# heights-no-branding.net
KiCad netlist of a schematic drawn in EAGLE
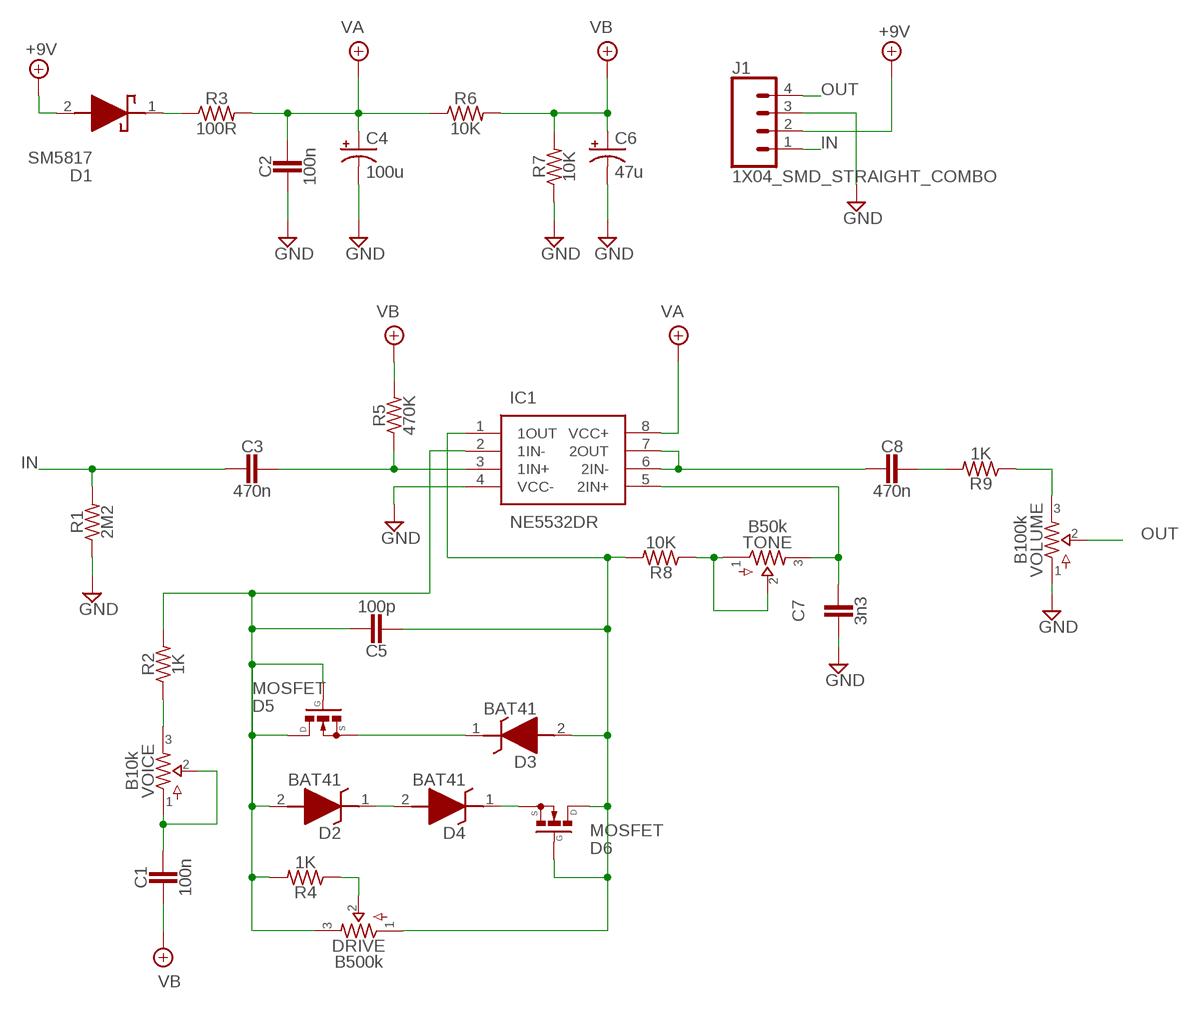
[diagram p0: schematic, sheet 1]

(export (version "E")
  (design (tool "Eeschema 10.0.6"))
  (components
    (comp (ref "C1")
      (value "100n")
      (footprint "eagle-import:RESISTOR_C1206")
      (libsource (lib "eagle-import") (part "CAP1206"))
    )
    (comp (ref "C2")
      (value "100n")
      (footprint "eagle-import:RESISTOR_R0603")
      (libsource (lib "eagle-import") (part "CAP0603"))
    )
    (comp (ref "C3")
      (value "470n")
      (footprint "eagle-import:RESISTOR_C1206")
      (libsource (lib "eagle-import") (part "CAP1206"))
    )
    (comp (ref "C4")
      (value "100u")
      (footprint "eagle-import:063_025")
      (libsource (lib "eagle-import") (part "0631"))
    )
    (comp (ref "C5")
      (value "100p")
      (footprint "eagle-import:RESISTOR_R0603")
      (libsource (lib "eagle-import") (part "CAP0603"))
    )
    (comp (ref "C6")
      (value "47u")
      (footprint "eagle-import:050_020_1")
      (libsource (lib "eagle-import") (part "0501"))
    )
    (comp (ref "C7")
      (value "3n3")
      (footprint "eagle-import:RESISTOR_R0603")
      (libsource (lib "eagle-import") (part "CAP0603"))
    )
    (comp (ref "C8")
      (value "470n")
      (footprint "eagle-import:RESISTOR_C1206")
      (libsource (lib "eagle-import") (part "CAP1206"))
    )
    (comp (ref "D1")
      (value "SM5817")
      (footprint "eagle-import:SOD3716X120N")
      (fields
        (field (name "MANUFACTURER_PART_NUMBER") "SM5817PL-TP")
        (field (name "MOUSER_PART_NUMBER") "833-SM5817PL-TP")
      )
      (libsource (lib "eagle-import") (part "SM5817PL-TP"))
    )
    (comp (ref "D2")
      (value "BAT41")
      (footprint "eagle-import:SODFL3718X130N")
      (fields
        (field (name "MANUFACTURER_PART_NUMBER") "MM1Z4733A")
        (field (name "MOUSER_PART_NUMBER") "637-MM1Z4733A")
      )
      (libsource (lib "eagle-import") (part "MM1Z4733A"))
    )
    (comp (ref "D3")
      (value "BAT41")
      (footprint "eagle-import:SODFL3718X130N")
      (fields
        (field (name "MANUFACTURER_PART_NUMBER") "MM1Z4733A")
        (field (name "MOUSER_PART_NUMBER") "637-MM1Z4733A")
      )
      (libsource (lib "eagle-import") (part "MM1Z4733A"))
    )
    (comp (ref "D4")
      (value "BAT41")
      (footprint "eagle-import:SODFL3718X130N")
      (fields
        (field (name "MANUFACTURER_PART_NUMBER") "MM1Z4733A")
        (field (name "MOUSER_PART_NUMBER") "637-MM1Z4733A")
      )
      (libsource (lib "eagle-import") (part "MM1Z4733A"))
    )
    (comp (ref "D5")
      (value "MOSFET")
      (footprint "eagle-import:TRANSISTOR_SOT23-GDS")
      (libsource (lib "eagle-import") (part "MOSFET"))
    )
    (comp (ref "D6")
      (value "MOSFET")
      (footprint "eagle-import:TRANSISTOR_SOT23-GDS")
      (libsource (lib "eagle-import") (part "MOSFET"))
    )
    (comp (ref "DRIVE")
      (value "B500k")
      (footprint "eagle-import:16MM_B.MOUNT")
      (libsource (lib "eagle-import") (part "16MM.1"))
    )
    (comp (ref "IC1")
      (value "NE5532DR")
      (footprint "eagle-import:SOIC127P600X175-8N")
      (fields (field (name "MOUSER_PART_NUMBER") "595-NE5532DR"))
      (libsource (lib "eagle-import") (part "NE5532DR"))
    )
    (comp (ref "J1")
      (value "1X04_SMD_STRAIGHT_COMBO")
      (footprint "eagle-import:1X04")
      (libsource (lib "eagle-import") (part "CONN_04PTH"))
    )
    (comp (ref "R1")
      (value "2M2")
      (footprint "eagle-import:RESISTOR_R0603")
      (libsource (lib "eagle-import") (part "RESISTOR0603"))
    )
    (comp (ref "R2")
      (value "1K")
      (footprint "eagle-import:RESISTOR_R0603")
      (libsource (lib "eagle-import") (part "RESISTOR0603"))
    )
    (comp (ref "R3")
      (value "100R")
      (footprint "eagle-import:RESISTOR_R0603")
      (libsource (lib "eagle-import") (part "RESISTOR0603"))
    )
    (comp (ref "R4")
      (value "1K")
      (footprint "eagle-import:RESISTOR_R0603")
      (libsource (lib "eagle-import") (part "RESISTOR0603"))
    )
    (comp (ref "R5")
      (value "470K")
      (footprint "eagle-import:RESISTOR_R0603")
      (libsource (lib "eagle-import") (part "RESISTOR0603"))
    )
    (comp (ref "R6")
      (value "10K")
      (footprint "eagle-import:RESISTOR_R0603")
      (libsource (lib "eagle-import") (part "RESISTOR0603"))
    )
    (comp (ref "R7")
      (value "10K")
      (footprint "eagle-import:RESISTOR_R0603")
      (libsource (lib "eagle-import") (part "RESISTOR0603"))
    )
    (comp (ref "R8")
      (value "10K")
      (footprint "eagle-import:RESISTOR_R0603")
      (libsource (lib "eagle-import") (part "RESISTOR0603"))
    )
    (comp (ref "R9")
      (value "1K")
      (footprint "eagle-import:RESISTOR_R0603")
      (libsource (lib "eagle-import") (part "RESISTOR0603"))
    )
    (comp (ref "TONE")
      (value "B50k")
      (footprint "eagle-import:16MM_B.MOUNT")
      (libsource (lib "eagle-import") (part "16MM.1"))
    )
    (comp (ref "VOICE")
      (value "B10k")
      (footprint "eagle-import:16MM_B.MOUNT")
      (libsource (lib "eagle-import") (part "16MM.1"))
    )
    (comp (ref "VOLUME")
      (value "B100k")
      (footprint "eagle-import:16MM_B.MOUNT")
      (libsource (lib "eagle-import") (part "16MM.1"))
    )
  )
  (nets
    (net (code "1") (name "+9V") (class "Default")
      (node (ref "D1") (pin "2") (pinfunction "A_2") (pintype "bidirectional"))
      (node (ref "J1") (pin "2") (pinfunction "2_2") (pintype "passive"))
    )
    (net (code "2") (name "/IN") (class "Default")
      (node (ref "C3") (pin "2") (pinfunction "2_2") (pintype "passive"))
      (node (ref "J1") (pin "1") (pinfunction "1_1") (pintype "passive"))
      (node (ref "R1") (pin "2") (pinfunction "2_2") (pintype "passive"))
    )
    (net (code "3") (name "/OUT") (class "Default")
      (node (ref "J1") (pin "4") (pinfunction "4_4") (pintype "passive"))
      (node (ref "VOLUME") (pin "2") (pinfunction "2_2") (pintype "passive"))
    )
    (net (code "4") (name "GND") (class "Default")
      (node (ref "C2") (pin "2") (pinfunction "2_2") (pintype "passive"))
      (node (ref "C4") (pin "-") (pinfunction "-_-") (pintype "passive"))
      (node (ref "C6") (pin "-") (pinfunction "-_-") (pintype "passive"))
      (node (ref "C7") (pin "2") (pinfunction "2_2") (pintype "passive"))
      (node (ref "IC1") (pin "4") (pinfunction "VCC-_4") (pintype "bidirectional"))
      (node (ref "J1") (pin "3") (pinfunction "3_3") (pintype "passive"))
      (node (ref "R1") (pin "1") (pinfunction "1_1") (pintype "passive"))
      (node (ref "R7") (pin "1") (pinfunction "1_1") (pintype "passive"))
      (node (ref "VOLUME") (pin "1") (pinfunction "1_1") (pintype "passive"))
    )
    (net (code "5") (name "Net-(C1-Pad1)") (class "Default")
      (node (ref "C1") (pin "1") (pinfunction "1_1") (pintype "passive"))
      (node (ref "VOICE") (pin "1") (pinfunction "1_1") (pintype "passive"))
      (node (ref "VOICE") (pin "2") (pinfunction "2_2") (pintype "passive"))
    )
    (net (code "6") (name "Net-(C8-Pad1)") (class "Default")
      (node (ref "C8") (pin "1") (pinfunction "1_1") (pintype "passive"))
      (node (ref "R9") (pin "2") (pinfunction "2_2") (pintype "passive"))
    )
    (net (code "7") (name "Net-(D1-K)") (class "Default")
      (node (ref "D1") (pin "1") (pinfunction "K_1") (pintype "bidirectional"))
      (node (ref "R3") (pin "1") (pinfunction "1_1") (pintype "passive"))
    )
    (net (code "8") (name "Net-(D2-A)") (class "Default")
      (node (ref "C5") (pin "1") (pinfunction "1_1") (pintype "passive"))
      (node (ref "D2") (pin "2") (pinfunction "A_2") (pintype "bidirectional"))
      (node (ref "D5") (pin "D") (pinfunction "D_D") (pintype "passive"))
      (node (ref "D5") (pin "G") (pinfunction "G_G") (pintype "passive"))
      (node (ref "DRIVE") (pin "3") (pinfunction "3_3") (pintype "passive"))
      (node (ref "IC1") (pin "2") (pinfunction "1IN-_2") (pintype "bidirectional"))
      (node (ref "R2") (pin "2") (pinfunction "2_2") (pintype "passive"))
      (node (ref "R4") (pin "2") (pinfunction "2_2") (pintype "passive"))
    )
    (net (code "9") (name "Net-(D2-K)") (class "Default")
      (node (ref "D2") (pin "1") (pinfunction "K_1") (pintype "bidirectional"))
      (node (ref "D4") (pin "2") (pinfunction "A_2") (pintype "bidirectional"))
    )
    (net (code "10") (name "Net-(D3-A)") (class "Default")
      (node (ref "C5") (pin "2") (pinfunction "2_2") (pintype "passive"))
      (node (ref "D3") (pin "2") (pinfunction "A_2") (pintype "bidirectional"))
      (node (ref "D6") (pin "D") (pinfunction "D_D") (pintype "passive"))
      (node (ref "D6") (pin "G") (pinfunction "G_G") (pintype "passive"))
      (node (ref "DRIVE") (pin "1") (pinfunction "1_1") (pintype "passive"))
      (node (ref "IC1") (pin "1") (pinfunction "1OUT_1") (pintype "bidirectional"))
      (node (ref "R8") (pin "2") (pinfunction "2_2") (pintype "passive"))
    )
    (net (code "11") (name "Net-(D3-K)") (class "Default")
      (node (ref "D3") (pin "1") (pinfunction "K_1") (pintype "bidirectional"))
      (node (ref "D5") (pin "S") (pinfunction "S_S") (pintype "passive"))
    )
    (net (code "12") (name "Net-(D4-K)") (class "Default")
      (node (ref "D4") (pin "1") (pinfunction "K_1") (pintype "bidirectional"))
      (node (ref "D6") (pin "S") (pinfunction "S_S") (pintype "passive"))
    )
    (net (code "13") (name "Net-(DRIVE-Pad2)") (class "Default")
      (node (ref "DRIVE") (pin "2") (pinfunction "2_2") (pintype "passive"))
      (node (ref "R4") (pin "1") (pinfunction "1_1") (pintype "passive"))
    )
    (net (code "14") (name "Net-(IC1-1IN+)") (class "Default")
      (node (ref "C3") (pin "1") (pinfunction "1_1") (pintype "passive"))
      (node (ref "IC1") (pin "3") (pinfunction "1IN+_3") (pintype "bidirectional"))
      (node (ref "R5") (pin "1") (pinfunction "1_1") (pintype "passive"))
    )
    (net (code "15") (name "Net-(IC1-2IN+)") (class "Default")
      (node (ref "C7") (pin "1") (pinfunction "1_1") (pintype "passive"))
      (node (ref "IC1") (pin "5") (pinfunction "2IN+_5") (pintype "bidirectional"))
      (node (ref "TONE") (pin "3") (pinfunction "3_3") (pintype "passive"))
    )
    (net (code "16") (name "Net-(IC1-2IN-)") (class "Default")
      (node (ref "C8") (pin "2") (pinfunction "2_2") (pintype "passive"))
      (node (ref "IC1") (pin "6") (pinfunction "2IN-_6") (pintype "bidirectional"))
      (node (ref "IC1") (pin "7") (pinfunction "2OUT_7") (pintype "bidirectional"))
    )
    (net (code "17") (name "Net-(R2-Pad1)") (class "Default")
      (node (ref "R2") (pin "1") (pinfunction "1_1") (pintype "passive"))
      (node (ref "VOICE") (pin "3") (pinfunction "3_3") (pintype "passive"))
    )
    (net (code "18") (name "Net-(R8-Pad1)") (class "Default")
      (node (ref "R8") (pin "1") (pinfunction "1_1") (pintype "passive"))
      (node (ref "TONE") (pin "1") (pinfunction "1_1") (pintype "passive"))
      (node (ref "TONE") (pin "2") (pinfunction "2_2") (pintype "passive"))
    )
    (net (code "19") (name "Net-(R9-Pad1)") (class "Default")
      (node (ref "R9") (pin "1") (pinfunction "1_1") (pintype "passive"))
      (node (ref "VOLUME") (pin "3") (pinfunction "3_3") (pintype "passive"))
    )
    (net (code "20") (name "VA") (class "Default")
      (node (ref "C2") (pin "1") (pinfunction "1_1") (pintype "passive"))
      (node (ref "C4") (pin "+") (pinfunction "+_+") (pintype "passive"))
      (node (ref "IC1") (pin "8") (pinfunction "VCC+_8") (pintype "bidirectional"))
      (node (ref "R3") (pin "2") (pinfunction "2_2") (pintype "passive"))
      (node (ref "R6") (pin "1") (pinfunction "1_1") (pintype "passive"))
    )
    (net (code "21") (name "VB") (class "Default")
      (node (ref "C1") (pin "2") (pinfunction "2_2") (pintype "passive"))
      (node (ref "C6") (pin "+") (pinfunction "+_+") (pintype "passive"))
      (node (ref "R5") (pin "2") (pinfunction "2_2") (pintype "passive"))
      (node (ref "R6") (pin "2") (pinfunction "2_2") (pintype "passive"))
      (node (ref "R7") (pin "2") (pinfunction "2_2") (pintype "passive"))
    )
  )
)
